# stm32.net
KiCad netlist of a schematic drawn in EasyEDA Pro
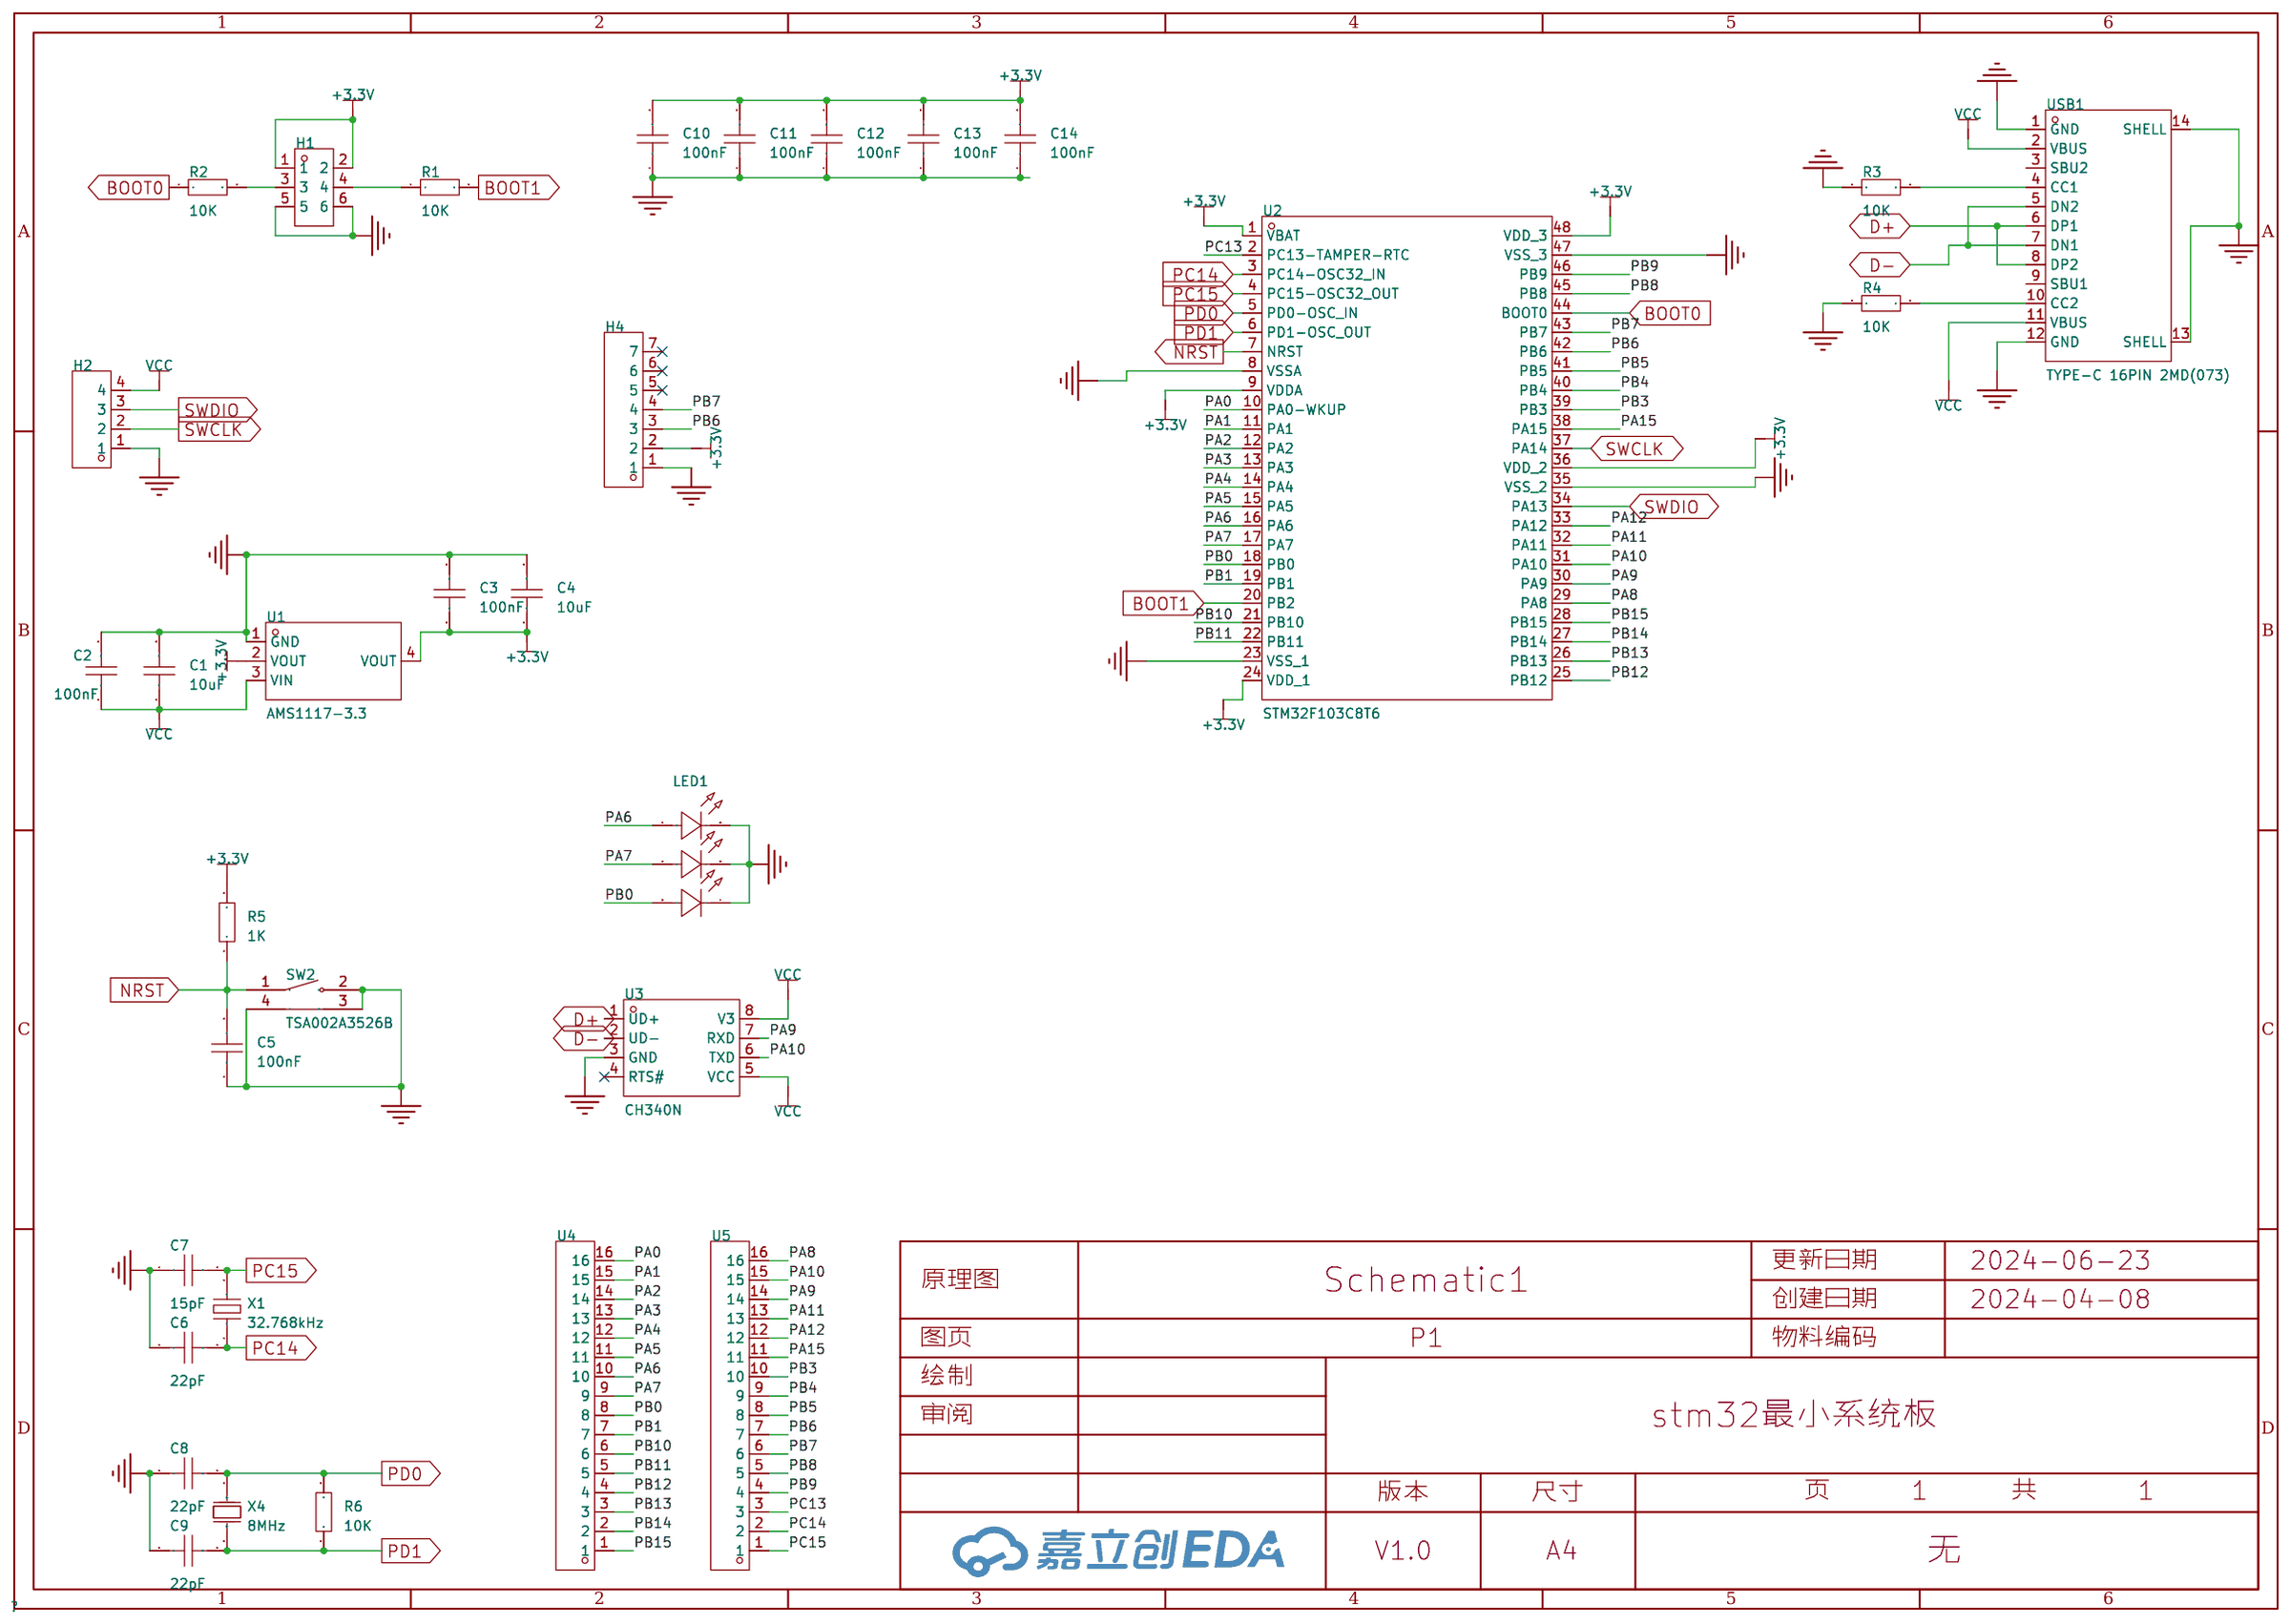
[diagram p0: schematic sheet]

(export (version "E")
  (design (tool "Eeschema 10.0.6"))
  (components
    (comp (ref "C1")
      (value "10uF")
      (footprint "easyedapro:C0603")
      (libsource (lib "easyedapro") (part "CapAcitance"))
    )
    (comp (ref "C2")
      (value "100nF")
      (footprint "easyedapro:C0603")
      (libsource (lib "easyedapro") (part "CapAcitance"))
    )
    (comp (ref "C3")
      (value "100nF")
      (footprint "easyedapro:C0603")
      (libsource (lib "easyedapro") (part "CapAcitance"))
    )
    (comp (ref "C4")
      (value "10uF")
      (footprint "easyedapro:C0603")
      (libsource (lib "easyedapro") (part "CapAcitance"))
    )
    (comp (ref "C5")
      (value "100nF")
      (footprint "easyedapro:C0603")
      (libsource (lib "easyedapro") (part "CapAcitance"))
    )
    (comp (ref "C6")
      (value "22pF")
      (footprint "easyedapro:C0603")
      (libsource (lib "easyedapro") (part "CapAcitance"))
    )
    (comp (ref "C7")
      (value "15pF")
      (footprint "easyedapro:C0603")
      (libsource (lib "easyedapro") (part "CapAcitance"))
    )
    (comp (ref "C8")
      (value "22pF")
      (footprint "easyedapro:C0603")
      (libsource (lib "easyedapro") (part "CapAcitance"))
    )
    (comp (ref "C9")
      (value "22pF")
      (footprint "easyedapro:C0603")
      (libsource (lib "easyedapro") (part "CapAcitance"))
    )
    (comp (ref "C10")
      (value "100nF")
      (footprint "easyedapro:C0603")
      (libsource (lib "easyedapro") (part "CapAcitance"))
    )
    (comp (ref "C11")
      (value "100nF")
      (footprint "easyedapro:C0603")
      (libsource (lib "easyedapro") (part "CapAcitance"))
    )
    (comp (ref "C12")
      (value "100nF")
      (footprint "easyedapro:C0603")
      (libsource (lib "easyedapro") (part "CapAcitance"))
    )
    (comp (ref "C13")
      (value "100nF")
      (footprint "easyedapro:C0603")
      (libsource (lib "easyedapro") (part "CapAcitance"))
    )
    (comp (ref "C14")
      (value "100nF")
      (footprint "easyedapro:C0603")
      (libsource (lib "easyedapro") (part "CapAcitance"))
    )
    (comp (ref "H1")
      (value "PZ254V-12-6P")
      (footprint "easyedapro:HDR-TH_6P-P2.54-V-M-R2-C3-S2.54")
      (fields (field (name "Manufacturer") "XFCN(兴飞)"))
      (libsource (lib "easyedapro") (part "PZ254V-12-6P"))
    )
    (comp (ref "H2")
      (value "PZ254V-11-04P")
      (footprint "easyedapro:HDR-TH_4P-P2.54-V-M")
      (fields (field (name "Manufacturer") "XFCN(兴飞)"))
      (libsource (lib "easyedapro") (part "PZ254V-11-04P_C2691448"))
    )
    (comp (ref "H4")
      (value "PZ254V-11-07P")
      (footprint "easyedapro:HDR-TH_7P-P2.54-V-M")
      (fields (field (name "Manufacturer") "XFCN(兴飞)"))
      (libsource (lib "easyedapro") (part "PZ254V-11-07P"))
    )
    (comp (ref "LED1")
      (value "TC5050RGBF08-3CJH-AF53A")
      (footprint "easyedapro:LED-SMD_6P-L5.0-W5.0-TL_TC5050RGBF08")
      (description "LED贴片5050RGB灯珠高亮红绿蓝三色0.2W")
      (fields (field (name "Manufacturer") "TCWIN(天成)"))
      (libsource (lib "easyedapro") (part "TC5050RGBF08-3CJH-AF53A"))
    )
    (comp (ref "R1") (value "10K") (footprint "easyedapro:R0603") (libsource (lib "easyedapro") (part "电阻")))
    (comp (ref "R2") (value "10K") (footprint "easyedapro:R0603") (libsource (lib "easyedapro") (part "电阻")))
    (comp (ref "R3") (value "10K") (footprint "easyedapro:R0603") (libsource (lib "easyedapro") (part "电阻")))
    (comp (ref "R4") (value "10K") (footprint "easyedapro:R0603") (libsource (lib "easyedapro") (part "电阻")))
    (comp (ref "R5") (value "1K") (footprint "easyedapro:R0603") (libsource (lib "easyedapro") (part "电阻")))
    (comp (ref "R6") (value "10K") (footprint "easyedapro:R0603") (libsource (lib "easyedapro") (part "电阻")))
    (comp (ref "SW2")
      (value "TSA002A3526B")
      (footprint "easyedapro:SW-SMD_TSA245G00D-250")
      (description "按钮形状:矩形按钮;安装方式:卧贴;开关长度:4.8mm;开关宽度:2mm;开关高度:3.5mm;触点电流:50mA;额定电压(AC):-;额定电压(DC):12V;机械寿命:-;")
      (fields (field (name "Manufacturer") "BZCN(博众电气)"))
      (libsource (lib "easyedapro") (part "TSA002A3526B"))
    )
    (comp (ref "U1")
      (value "AMS1117-3.3")
      (footprint "easyedapro:SOT-223-3_L6.5-W3.4-P2.30-LS7.0-BR")
      (description "输出类型:固定;最大输入电压:-;输出电压:3.3V;最大输出电流:1A;电源纹波抑制比(PSRR):72dB@(120Hz);输出极性:正极;")
      (fields (field (name "Manufacturer") "AMS"))
      (libsource (lib "easyedapro") (part "AMS1117-3.3"))
    )
    (comp (ref "U2")
      (value "STM32F103C8T6")
      (footprint "easyedapro:LQFP-48_L7.0-W7.0-P0.50-LS9.0-BL")
      (description "CPU内核:ARM-M3;程序存储容量:64KB;RAM总容量:20KB;GPIO端口数量:37;工作电压范围:2V~3.6V;CPU最大主频:72MHz;程序存储器类型:FLASH;")
      (fields (field (name "Manufacturer") "ST(意法半导体)"))
      (libsource (lib "easyedapro") (part "STM32F103C8T6"))
    )
    (comp (ref "U3")
      (value "CH340N")
      (footprint "easyedapro:SOP-8_L4.9-W3.9-P1.27-LS6.0-BL")
      (fields (field (name "Manufacturer") "WCH(南京沁恒)"))
      (libsource (lib "easyedapro") (part "CH340N_C2977777"))
    )
    (comp (ref "U4")
      (value "ZX-PZ2.54-1-16PZZ")
      (footprint "easyedapro:HDR-TH_16P-P2.54-V-M-2")
      (fields (field (name "Manufacturer") "Megastar(兆星)"))
      (libsource (lib "easyedapro") (part "ZX-PZ2.54-1-16PZZ"))
    )
    (comp (ref "U5")
      (value "ZX-PZ2.54-1-16PZZ")
      (footprint "easyedapro:HDR-TH_16P-P2.54-V-M-2")
      (fields (field (name "Manufacturer") "Megastar(兆星)"))
      (libsource (lib "easyedapro") (part "ZX-PZ2.54-1-16PZZ"))
    )
    (comp (ref "USB1")
      (value "TYPE-C 16PIN 2MD(073)")
      (footprint "easyedapro:USB-C-SMD_TYPE-C-6PIN-2MD-073")
      (description "连接器类型:Type-C;标准:-;公母:母;端口数量:1;触点数量:16P;安装方式:卧贴;额定电流 - 电源:5A;工作温度范围:-25°C~+85°C;")
      (fields (field (name "Manufacturer") "SHOU HAN(首韩)"))
      (libsource (lib "easyedapro") (part "TYPE-C 16PIN 2MD(073)"))
    )
    (comp (ref "X1")
      (value "32.768kHz")
      (footprint "easyedapro:OSC-SMD_L3.2-W1.5")
      (description "晶振类型:贴片晶振;频率:32.768kHz;常温频差:±20ppm;外接负载电容:12.5pF;频率稳定度(全温):-;")
      (fields (field (name "Manufacturer Part") "X321532768KGD2SI") (field (name "Manufacturer") "YXC(扬兴晶振)"))
      (libsource (lib "easyedapro") (part "X321532768KGD2SI"))
    )
    (comp (ref "X4")
      (value "8MHz")
      (footprint "easyedapro:CRYSTAL-SMD_L11.5-W4.8-LS12.7")
      (description "晶振类型:贴片晶振;频率:8MHz;常温频差:±20ppm;外接负载电容:20pF;频率稳定度(全温):±30ppm;")
      (fields (field (name "Manufacturer Part") "X49SM8MSD2SC") (field (name "Manufacturer") "YXC(扬兴晶振)"))
      (libsource (lib "easyedapro") (part "X49SM8MSD2SC"))
    )
  )
  (nets
    (net (code "1") (name "+3.3V") (class "Default")
      (node (ref "C10") (pin "2") (pinfunction "2_2") (pintype "input"))
      (node (ref "C11") (pin "2") (pinfunction "2_2") (pintype "input"))
      (node (ref "C12") (pin "2") (pinfunction "2_2") (pintype "input"))
      (node (ref "C13") (pin "2") (pinfunction "2_2") (pintype "input"))
      (node (ref "C14") (pin "2") (pinfunction "2_2") (pintype "input"))
      (node (ref "C3") (pin "1") (pinfunction "1_1") (pintype "input"))
      (node (ref "C4") (pin "1") (pinfunction "1_1") (pintype "input"))
      (node (ref "H1") (pin "1") (pinfunction "1_1") (pintype "unspecified"))
      (node (ref "H1") (pin "2") (pinfunction "2_2") (pintype "unspecified"))
      (node (ref "H4") (pin "2") (pinfunction "2_2") (pintype "unspecified"))
      (node (ref "R5") (pin "2") (pinfunction "2_2") (pintype "input"))
      (node (ref "U1") (pin "2") (pinfunction "VOUT_2") (pintype "unspecified"))
      (node (ref "U1") (pin "4") (pinfunction "VOUT_4") (pintype "unspecified"))
      (node (ref "U2") (pin "1") (pinfunction "VBAT_1") (pintype "unspecified"))
      (node (ref "U2") (pin "24") (pinfunction "VDD_1_24") (pintype "unspecified"))
      (node (ref "U2") (pin "36") (pinfunction "VDD_2_36") (pintype "unspecified"))
      (node (ref "U2") (pin "48") (pinfunction "VDD_3_48") (pintype "unspecified"))
      (node (ref "U2") (pin "9") (pinfunction "VDDA_9") (pintype "unspecified"))
    )
    (net (code "2") (name "/PA0") (class "Default")
      (node (ref "U2") (pin "10") (pinfunction "PA0-WKUP_10") (pintype "unspecified"))
      (node (ref "U4") (pin "16") (pinfunction "16_16") (pintype "unspecified"))
    )
    (net (code "3") (name "/PA1") (class "Default")
      (node (ref "U2") (pin "11") (pinfunction "PA1_11") (pintype "unspecified"))
      (node (ref "U4") (pin "15") (pinfunction "15_15") (pintype "unspecified"))
    )
    (net (code "4") (name "/PA2") (class "Default")
      (node (ref "U2") (pin "12") (pinfunction "PA2_12") (pintype "unspecified"))
      (node (ref "U4") (pin "14") (pinfunction "14_14") (pintype "unspecified"))
    )
    (net (code "5") (name "/PA3") (class "Default")
      (node (ref "U2") (pin "13") (pinfunction "PA3_13") (pintype "unspecified"))
      (node (ref "U4") (pin "13") (pinfunction "13_13") (pintype "unspecified"))
    )
    (net (code "6") (name "/PA4") (class "Default")
      (node (ref "U2") (pin "14") (pinfunction "PA4_14") (pintype "unspecified"))
      (node (ref "U4") (pin "12") (pinfunction "12_12") (pintype "unspecified"))
    )
    (net (code "7") (name "/PA5") (class "Default")
      (node (ref "U2") (pin "15") (pinfunction "PA5_15") (pintype "unspecified"))
      (node (ref "U4") (pin "11") (pinfunction "11_11") (pintype "unspecified"))
    )
    (net (code "8") (name "/PA6") (class "Default")
      (node (ref "LED1") (pin "1") (pinfunction "+_1") (pintype "unspecified"))
      (node (ref "U2") (pin "16") (pinfunction "PA6_16") (pintype "unspecified"))
      (node (ref "U4") (pin "10") (pinfunction "10_10") (pintype "unspecified"))
    )
    (net (code "9") (name "/PA7") (class "Default")
      (node (ref "LED1") (pin "2") (pinfunction "+_2") (pintype "unspecified"))
      (node (ref "U2") (pin "17") (pinfunction "PA7_17") (pintype "unspecified"))
      (node (ref "U4") (pin "9") (pinfunction "9_9") (pintype "unspecified"))
    )
    (net (code "10") (name "/PA8") (class "Default")
      (node (ref "U2") (pin "29") (pinfunction "PA8_29") (pintype "unspecified"))
      (node (ref "U5") (pin "16") (pinfunction "16_16") (pintype "unspecified"))
    )
    (net (code "11") (name "/PA9") (class "Default")
      (node (ref "U2") (pin "30") (pinfunction "PA9_30") (pintype "unspecified"))
      (node (ref "U3") (pin "7") (pinfunction "RXD_7") (pintype "unspecified"))
      (node (ref "U5") (pin "14") (pinfunction "14_14") (pintype "unspecified"))
    )
    (net (code "12") (name "/PA10") (class "Default")
      (node (ref "U2") (pin "31") (pinfunction "PA10_31") (pintype "unspecified"))
      (node (ref "U3") (pin "6") (pinfunction "TXD_6") (pintype "unspecified"))
      (node (ref "U5") (pin "15") (pinfunction "15_15") (pintype "unspecified"))
    )
    (net (code "13") (name "/PA11") (class "Default")
      (node (ref "U2") (pin "32") (pinfunction "PA11_32") (pintype "unspecified"))
      (node (ref "U5") (pin "13") (pinfunction "13_13") (pintype "unspecified"))
    )
    (net (code "14") (name "/PA12") (class "Default")
      (node (ref "U2") (pin "33") (pinfunction "PA12_33") (pintype "unspecified"))
      (node (ref "U5") (pin "12") (pinfunction "12_12") (pintype "unspecified"))
    )
    (net (code "15") (name "/PA15") (class "Default")
      (node (ref "U2") (pin "38") (pinfunction "PA15_38") (pintype "unspecified"))
      (node (ref "U5") (pin "11") (pinfunction "11_11") (pintype "unspecified"))
    )
    (net (code "16") (name "/PB0") (class "Default")
      (node (ref "LED1") (pin "3") (pinfunction "+_3") (pintype "unspecified"))
      (node (ref "U2") (pin "18") (pinfunction "PB0_18") (pintype "unspecified"))
      (node (ref "U4") (pin "8") (pinfunction "8_8") (pintype "unspecified"))
    )
    (net (code "17") (name "/PB1") (class "Default")
      (node (ref "U2") (pin "19") (pinfunction "PB1_19") (pintype "unspecified"))
      (node (ref "U4") (pin "7") (pinfunction "7_7") (pintype "unspecified"))
    )
    (net (code "18") (name "/PB3") (class "Default")
      (node (ref "U2") (pin "39") (pinfunction "PB3_39") (pintype "unspecified"))
      (node (ref "U5") (pin "10") (pinfunction "10_10") (pintype "unspecified"))
    )
    (net (code "19") (name "/PB4") (class "Default")
      (node (ref "U2") (pin "40") (pinfunction "PB4_40") (pintype "unspecified"))
      (node (ref "U5") (pin "9") (pinfunction "9_9") (pintype "unspecified"))
    )
    (net (code "20") (name "/PB5") (class "Default")
      (node (ref "U2") (pin "41") (pinfunction "PB5_41") (pintype "unspecified"))
      (node (ref "U5") (pin "8") (pinfunction "8_8") (pintype "unspecified"))
    )
    (net (code "21") (name "/PB6") (class "Default")
      (node (ref "H4") (pin "3") (pinfunction "3_3") (pintype "unspecified"))
      (node (ref "U2") (pin "42") (pinfunction "PB6_42") (pintype "unspecified"))
      (node (ref "U5") (pin "7") (pinfunction "7_7") (pintype "unspecified"))
    )
    (net (code "22") (name "/PB7") (class "Default")
      (node (ref "H4") (pin "4") (pinfunction "4_4") (pintype "unspecified"))
      (node (ref "U2") (pin "43") (pinfunction "PB7_43") (pintype "unspecified"))
      (node (ref "U5") (pin "6") (pinfunction "6_6") (pintype "unspecified"))
    )
    (net (code "23") (name "/PB8") (class "Default")
      (node (ref "U2") (pin "45") (pinfunction "PB8_45") (pintype "unspecified"))
      (node (ref "U5") (pin "5") (pinfunction "5_5") (pintype "unspecified"))
    )
    (net (code "24") (name "/PB9") (class "Default")
      (node (ref "U2") (pin "46") (pinfunction "PB9_46") (pintype "unspecified"))
      (node (ref "U5") (pin "4") (pinfunction "4_4") (pintype "unspecified"))
    )
    (net (code "25") (name "/PB10") (class "Default")
      (node (ref "U2") (pin "21") (pinfunction "PB10_21") (pintype "unspecified"))
      (node (ref "U4") (pin "6") (pinfunction "6_6") (pintype "unspecified"))
    )
    (net (code "26") (name "/PB11") (class "Default")
      (node (ref "U2") (pin "22") (pinfunction "PB11_22") (pintype "unspecified"))
      (node (ref "U4") (pin "5") (pinfunction "5_5") (pintype "unspecified"))
    )
    (net (code "27") (name "/PB12") (class "Default")
      (node (ref "U2") (pin "25") (pinfunction "PB12_25") (pintype "unspecified"))
      (node (ref "U4") (pin "4") (pinfunction "4_4") (pintype "unspecified"))
    )
    (net (code "28") (name "/PB13") (class "Default")
      (node (ref "U2") (pin "26") (pinfunction "PB13_26") (pintype "unspecified"))
      (node (ref "U4") (pin "3") (pinfunction "3_3") (pintype "unspecified"))
    )
    (net (code "29") (name "/PB14") (class "Default")
      (node (ref "U2") (pin "27") (pinfunction "PB14_27") (pintype "unspecified"))
      (node (ref "U4") (pin "2") (pinfunction "2_2") (pintype "unspecified"))
    )
    (net (code "30") (name "/PB15") (class "Default")
      (node (ref "U2") (pin "28") (pinfunction "PB15_28") (pintype "unspecified"))
      (node (ref "U4") (pin "1") (pinfunction "1_1") (pintype "unspecified"))
    )
    (net (code "31") (name "/PC13") (class "Default")
      (node (ref "U2") (pin "2") (pinfunction "PC13-TAMPER-RTC_2") (pintype "unspecified"))
      (node (ref "U5") (pin "3") (pinfunction "3_3") (pintype "unspecified"))
    )
    (net (code "32") (name "BOOT0") (class "Default")
      (node (ref "R2") (pin "1") (pinfunction "1_1") (pintype "input"))
      (node (ref "U2") (pin "44") (pinfunction "BOOT0_44") (pintype "unspecified"))
    )
    (net (code "33") (name "BOOT1") (class "Default")
      (node (ref "R1") (pin "2") (pinfunction "2_2") (pintype "input"))
      (node (ref "U2") (pin "20") (pinfunction "PB2_20") (pintype "unspecified"))
    )
    (net (code "34") (name "D+") (class "Default")
      (node (ref "U3") (pin "1") (pinfunction "UD+_1") (pintype "unspecified"))
      (node (ref "USB1") (pin "6") (pinfunction "DP1_6") (pintype "unspecified"))
      (node (ref "USB1") (pin "8") (pinfunction "DP2_8") (pintype "unspecified"))
    )
    (net (code "35") (name "D-") (class "Default")
      (node (ref "U3") (pin "2") (pinfunction "UD-_2") (pintype "unspecified"))
      (node (ref "USB1") (pin "5") (pinfunction "DN2_5") (pintype "unspecified"))
      (node (ref "USB1") (pin "7") (pinfunction "DN1_7") (pintype "unspecified"))
    )
    (net (code "36") (name "GND") (class "Default")
      (node (ref "C1") (pin "2") (pinfunction "2_2") (pintype "input"))
      (node (ref "C10") (pin "1") (pinfunction "1_1") (pintype "input"))
      (node (ref "C11") (pin "1") (pinfunction "1_1") (pintype "input"))
      (node (ref "C12") (pin "1") (pinfunction "1_1") (pintype "input"))
      (node (ref "C13") (pin "1") (pinfunction "1_1") (pintype "input"))
      (node (ref "C14") (pin "1") (pinfunction "1_1") (pintype "input"))
      (node (ref "C2") (pin "2") (pinfunction "2_2") (pintype "input"))
      (node (ref "C3") (pin "2") (pinfunction "2_2") (pintype "input"))
      (node (ref "C4") (pin "2") (pinfunction "2_2") (pintype "input"))
      (node (ref "C5") (pin "1") (pinfunction "1_1") (pintype "input"))
      (node (ref "C6") (pin "1") (pinfunction "1_1") (pintype "input"))
      (node (ref "C7") (pin "1") (pinfunction "1_1") (pintype "input"))
      (node (ref "C8") (pin "1") (pinfunction "1_1") (pintype "input"))
      (node (ref "C9") (pin "1") (pinfunction "1_1") (pintype "input"))
      (node (ref "H1") (pin "5") (pinfunction "5_5") (pintype "unspecified"))
      (node (ref "H1") (pin "6") (pinfunction "6_6") (pintype "unspecified"))
      (node (ref "H2") (pin "1") (pinfunction "1_1") (pintype "unspecified"))
      (node (ref "H4") (pin "1") (pinfunction "1_1") (pintype "unspecified"))
      (node (ref "LED1") (pin "4") (pinfunction "-_4") (pintype "unspecified"))
      (node (ref "LED1") (pin "5") (pinfunction "-_5") (pintype "unspecified"))
      (node (ref "LED1") (pin "6") (pinfunction "-_6") (pintype "unspecified"))
      (node (ref "R3") (pin "1") (pinfunction "1_1") (pintype "input"))
      (node (ref "R4") (pin "1") (pinfunction "1_1") (pintype "input"))
      (node (ref "SW2") (pin "2") (pinfunction "2_2") (pintype "unspecified"))
      (node (ref "SW2") (pin "3") (pinfunction "3_3") (pintype "unspecified"))
      (node (ref "SW2") (pin "4") (pinfunction "4_4") (pintype "unspecified"))
      (node (ref "U1") (pin "1") (pinfunction "GND_1") (pintype "unspecified"))
      (node (ref "U2") (pin "23") (pinfunction "VSS_1_23") (pintype "unspecified"))
      (node (ref "U2") (pin "35") (pinfunction "VSS_2_35") (pintype "unspecified"))
      (node (ref "U2") (pin "47") (pinfunction "VSS_3_47") (pintype "unspecified"))
      (node (ref "U2") (pin "8") (pinfunction "VSSA_8") (pintype "unspecified"))
      (node (ref "U3") (pin "3") (pinfunction "GND_3") (pintype "unspecified"))
      (node (ref "USB1") (pin "1") (pinfunction "GND_1") (pintype "unspecified"))
      (node (ref "USB1") (pin "12") (pinfunction "GND_12") (pintype "unspecified"))
      (node (ref "USB1") (pin "13") (pinfunction "SHELL_13") (pintype "unspecified"))
      (node (ref "USB1") (pin "14") (pinfunction "SHELL_14") (pintype "unspecified"))
    )
    (net (code "37") (name "NRST") (class "Default")
      (node (ref "C5") (pin "2") (pinfunction "2_2") (pintype "input"))
      (node (ref "R5") (pin "1") (pinfunction "1_1") (pintype "input"))
      (node (ref "SW2") (pin "1") (pinfunction "1_1") (pintype "unspecified"))
      (node (ref "U2") (pin "7") (pinfunction "NRST_7") (pintype "unspecified"))
    )
    (net (code "38") (name "Net-(H1-Pad3)") (class "Default")
      (node (ref "H1") (pin "3") (pinfunction "3_3") (pintype "unspecified"))
      (node (ref "R2") (pin "2") (pinfunction "2_2") (pintype "input"))
    )
    (net (code "39") (name "Net-(H1-Pad4)") (class "Default")
      (node (ref "H1") (pin "4") (pinfunction "4_4") (pintype "unspecified"))
      (node (ref "R1") (pin "1") (pinfunction "1_1") (pintype "input"))
    )
    (net (code "40") (name "Net-(USB1-CC1)") (class "Default")
      (node (ref "R3") (pin "2") (pinfunction "2_2") (pintype "input"))
      (node (ref "USB1") (pin "4") (pinfunction "CC1_4") (pintype "unspecified"))
    )
    (net (code "41") (name "Net-(USB1-CC2)") (class "Default")
      (node (ref "R4") (pin "2") (pinfunction "2_2") (pintype "input"))
      (node (ref "USB1") (pin "10") (pinfunction "CC2_10") (pintype "unspecified"))
    )
    (net (code "42") (name "PC14") (class "Default")
      (node (ref "C6") (pin "2") (pinfunction "2_2") (pintype "input"))
      (node (ref "U2") (pin "3") (pinfunction "PC14-OSC32_IN_3") (pintype "unspecified"))
      (node (ref "U5") (pin "2") (pinfunction "2_2") (pintype "unspecified"))
      (node (ref "X1") (pin "1") (pinfunction "1_1") (pintype "input"))
    )
    (net (code "43") (name "PC15") (class "Default")
      (node (ref "C7") (pin "2") (pinfunction "2_2") (pintype "input"))
      (node (ref "U2") (pin "4") (pinfunction "PC15-OSC32_OUT_4") (pintype "unspecified"))
      (node (ref "U5") (pin "1") (pinfunction "1_1") (pintype "unspecified"))
      (node (ref "X1") (pin "2") (pinfunction "2_2") (pintype "input"))
    )
    (net (code "44") (name "PD0") (class "Default")
      (node (ref "C8") (pin "2") (pinfunction "2_2") (pintype "input"))
      (node (ref "R6") (pin "2") (pinfunction "2_2") (pintype "input"))
      (node (ref "U2") (pin "5") (pinfunction "PD0-OSC_IN_5") (pintype "unspecified"))
      (node (ref "X4") (pin "1") (pinfunction "OSC1_1") (pintype "input"))
    )
    (net (code "45") (name "PD1") (class "Default")
      (node (ref "C9") (pin "2") (pinfunction "2_2") (pintype "input"))
      (node (ref "R6") (pin "1") (pinfunction "1_1") (pintype "input"))
      (node (ref "U2") (pin "6") (pinfunction "PD1-OSC_OUT_6") (pintype "unspecified"))
      (node (ref "X4") (pin "2") (pinfunction "OSC2_2") (pintype "input"))
    )
    (net (code "46") (name "SWCLK") (class "Default")
      (node (ref "H2") (pin "2") (pinfunction "2_2") (pintype "unspecified"))
      (node (ref "U2") (pin "37") (pinfunction "PA14_37") (pintype "unspecified"))
    )
    (net (code "47") (name "SWDIO") (class "Default")
      (node (ref "H2") (pin "3") (pinfunction "3_3") (pintype "unspecified"))
      (node (ref "U2") (pin "34") (pinfunction "PA13_34") (pintype "unspecified"))
    )
    (net (code "48") (name "VCC") (class "Default")
      (node (ref "C1") (pin "1") (pinfunction "1_1") (pintype "input"))
      (node (ref "C2") (pin "1") (pinfunction "1_1") (pintype "input"))
      (node (ref "H2") (pin "4") (pinfunction "4_4") (pintype "unspecified"))
      (node (ref "U1") (pin "3") (pinfunction "VIN_3") (pintype "unspecified"))
      (node (ref "U3") (pin "5") (pinfunction "VCC_5") (pintype "unspecified"))
      (node (ref "U3") (pin "8") (pinfunction "V3_8") (pintype "unspecified"))
      (node (ref "USB1") (pin "11") (pinfunction "VBUS_11") (pintype "unspecified"))
      (node (ref "USB1") (pin "2") (pinfunction "VBUS_2") (pintype "unspecified"))
    )
    (net (code "49") (name "unconnected-(H4-Pad5)") (class "Default")
      (node (ref "H4") (pin "5") (pinfunction "5_5") (pintype "unspecified+no_connect"))
    )
    (net (code "50") (name "unconnected-(H4-Pad6)") (class "Default")
      (node (ref "H4") (pin "6") (pinfunction "6_6") (pintype "unspecified+no_connect"))
    )
    (net (code "51") (name "unconnected-(H4-Pad7)") (class "Default")
      (node (ref "H4") (pin "7") (pinfunction "7_7") (pintype "unspecified+no_connect"))
    )
    (net (code "52") (name "unconnected-(U3-RTS#-Pad4)") (class "Default")
      (node (ref "U3") (pin "4") (pinfunction "RTS#_4") (pintype "unspecified+no_connect"))
    )
    (net (code "53") (name "unconnected-(USB1-SBU1-Pad9)") (class "Default")
      (node (ref "USB1") (pin "9") (pinfunction "SBU1_9") (pintype "unspecified"))
    )
    (net (code "54") (name "unconnected-(USB1-SBU2-Pad3)") (class "Default")
      (node (ref "USB1") (pin "3") (pinfunction "SBU2_3") (pintype "unspecified"))
    )
  )
)
